# Redox1_1_Integration_Trial.net
KiCad netlist of a schematic drawn in EAGLE
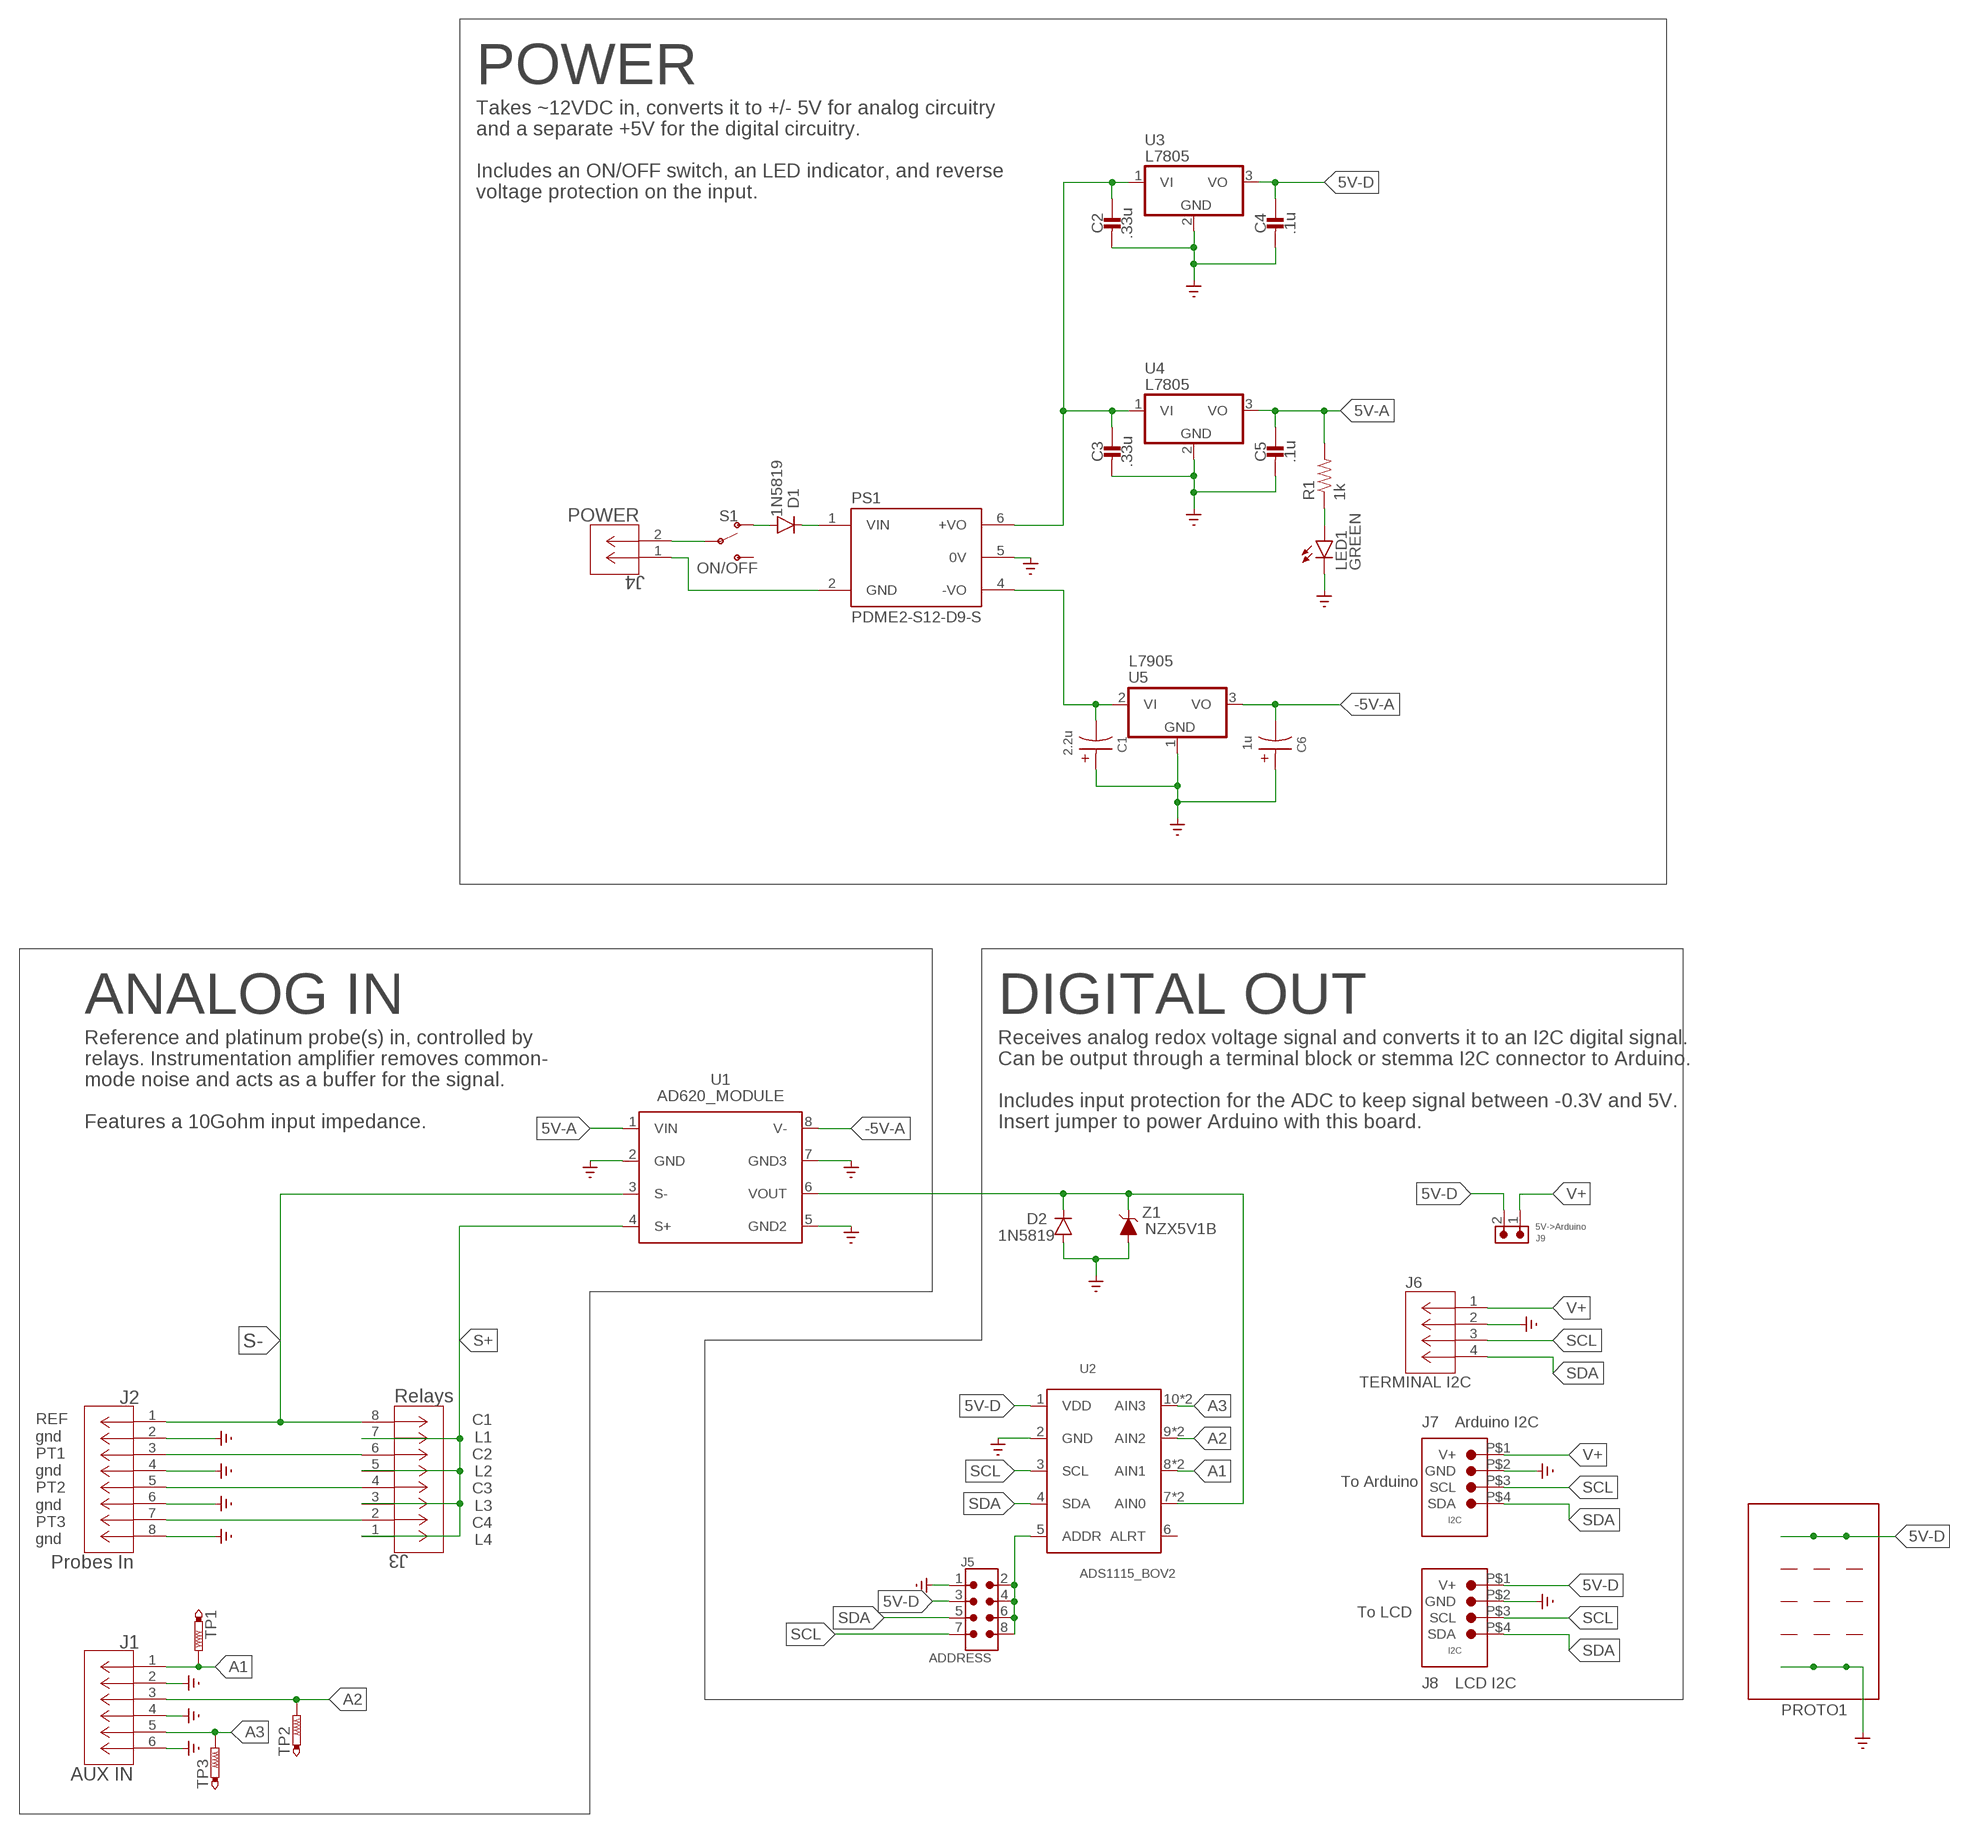
[diagram p0: schematic, sheet 1]

(export (version "E")
  (design (tool "Eeschema 10.0.6"))
  (components
    (comp (ref "C1")
      (value "2.2u")
      (footprint "eagle-import:E2,5-5")
      (libsource (lib "eagle-import") (part "CAP_POLAR_TH5MM"))
    )
    (comp (ref "C2")
      (value ".33u")
      (footprint "eagle-import:THCAPCERAMIC")
      (libsource (lib "eagle-import") (part "CAP-TH-CERAMIC"))
    )
    (comp (ref "C3")
      (value ".33u")
      (footprint "eagle-import:THCAPCERAMIC")
      (libsource (lib "eagle-import") (part "CAP-TH-CERAMIC"))
    )
    (comp (ref "C4")
      (value ".1u")
      (footprint "eagle-import:THCAPCERAMIC")
      (libsource (lib "eagle-import") (part "CAP-TH-CERAMIC"))
    )
    (comp (ref "C5")
      (value ".1u")
      (footprint "eagle-import:THCAPCERAMIC")
      (libsource (lib "eagle-import") (part "CAP-TH-CERAMIC"))
    )
    (comp (ref "C6")
      (value "1u")
      (footprint "eagle-import:E2,5-5")
      (libsource (lib "eagle-import") (part "CAP_POLAR_TH5MM"))
    )
    (comp (ref "D1")
      (value "1N5819")
      (footprint "eagle-import:DIODE-TH")
      (libsource (lib "eagle-import") (part "DIODE-TH"))
    )
    (comp (ref "D2")
      (value "1N5819")
      (footprint "eagle-import:DIODE-TH")
      (libsource (lib "eagle-import") (part "DIODE-TH"))
    )
    (comp (ref "J1")
      (value "AUX IN")
      (footprint "eagle-import:6PIN_TERMINAL_5MM")
      (libsource (lib "eagle-import") (part "6PIN_TERMINAL_5MM"))
    )
    (comp (ref "J2")
      (value "Probes In")
      (footprint "eagle-import:8PIN_TERMINAL_5MM")
      (libsource (lib "eagle-import") (part "8PIN_TERMINAL_5MM"))
    )
    (comp (ref "J3")
      (value "Relays")
      (footprint "eagle-import:8PIN_TERMINAL_5MM")
      (libsource (lib "eagle-import") (part "8PIN_TERMINAL_5MM"))
    )
    (comp (ref "J4")
      (value "POWER")
      (footprint "eagle-import:CONN2_710002_WRE")
      (fields
        (field (name "MANUFACTURER_PART_NUMBER") "691137710002")
        (field (name "COPYRIGHT") "Copyright (C) 2023 Ultra Librarian. All rights reserved.")
      )
      (libsource (lib "eagle-import") (part "2PIN_TERMINAL_5MM"))
    )
    (comp (ref "J5")
      (value "ADDRESS")
      (footprint "eagle-import:61300821121")
      (libsource (lib "eagle-import") (part "6130XX21121_61300821121"))
    )
    (comp (ref "J6")
      (value "TERMINAL I2C")
      (footprint "eagle-import:4PIN_TERMINAL_5MM")
      (libsource (lib "eagle-import") (part "4PIN_TERMINAL_5MM"))
    )
    (comp (ref "J7")
      (value "Arduino I2C")
      (footprint "eagle-import:JST_PH_4PIN")
      (libsource (lib "eagle-import") (part "JST_PH_4PIN_STEMMA"))
    )
    (comp (ref "J8")
      (value "LCD I2C")
      (footprint "eagle-import:JST_PH_4PIN")
      (libsource (lib "eagle-import") (part "JST_PH_4PIN_STEMMA"))
    )
    (comp (ref "J9")
      (value "5V->Arduino")
      (footprint "eagle-import:61300211121")
      (libsource (lib "eagle-import") (part "1X2MALEPIN"))
    )
    (comp (ref "LED1")
      (value "GREEN")
      (footprint "eagle-import:LED-5MM-TH")
      (libsource (lib "eagle-import") (part "LED-TH(5MM)"))
    )
    (comp (ref "PROTO1")
      (value "PROTO_AREA_5X3")
      (footprint "eagle-import:PROTO_AREA_5X3")
      (libsource (lib "eagle-import") (part "PROTO_AREA_5X3"))
    )
    (comp (ref "PS1")
      (value "PDME2-S12-D9-S")
      (footprint "eagle-import:CONV_PDME2-S12-D9-S")
      (fields (field (name "MANUFACTURER") "CUI Inc"))
      (libsource (lib "eagle-import") (part "PDME2-S12-D9-S"))
    )
    (comp (ref "R1")
      (value "1k")
      (footprint "eagle-import:THRESISTOR")
      (libsource (lib "eagle-import") (part "RESISTOR-TH"))
    )
    (comp (ref "S1")
      (value "ON/OFF")
      (footprint "eagle-import:TT11_SPDT")
      (libsource (lib "eagle-import") (part "SPDT_TT11_TH"))
    )
    (comp (ref "TP1")
      (value "PTR1PAD1-13")
      (footprint "eagle-import:P1-13")
      (libsource (lib "eagle-import") (part "PTR1PAD1-13"))
    )
    (comp (ref "TP2")
      (value "PTR1PAD1-13")
      (footprint "eagle-import:P1-13")
      (libsource (lib "eagle-import") (part "PTR1PAD1-13"))
    )
    (comp (ref "TP3")
      (value "PTR1PAD1-13")
      (footprint "eagle-import:P1-13")
      (libsource (lib "eagle-import") (part "PTR1PAD1-13"))
    )
    (comp (ref "U1")
      (value "AD620_MODULE")
      (footprint "eagle-import:AD620_MODULE")
      (libsource (lib "eagle-import") (part "AD620_MODULE"))
    )
    (comp (ref "U2")
      (value "ADS1115_BOV2")
      (footprint "eagle-import:ADS1115_V2")
      (libsource (lib "eagle-import") (part "ADS1115_BOV2"))
    )
    (comp (ref "U3")
      (value "L7805")
      (footprint "eagle-import:TO220V")
      (libsource (lib "eagle-import") (part "78TV05"))
    )
    (comp (ref "U4")
      (value "L7805")
      (footprint "eagle-import:TO220V")
      (libsource (lib "eagle-import") (part "78TV05"))
    )
    (comp (ref "U5")
      (value "L7905")
      (footprint "eagle-import:TO220V")
      (libsource (lib "eagle-import") (part "L79REGULATORTO220V"))
    )
    (comp (ref "Z1")
      (value "NZX5V1B")
      (footprint "eagle-import:DIODE-TH")
      (libsource (lib "eagle-import") (part "ZENER"))
    )
  )
  (nets
    (net (code "1") (name "-5V-A") (class "Default")
      (node (ref "C6") (pin "-") (pinfunction "-_-") (pintype "passive"))
      (node (ref "U1") (pin "8") (pinfunction "V-_8") (pintype "bidirectional"))
      (node (ref "U5") (pin "3") (pinfunction "VO_3") (pintype "passive"))
    )
    (net (code "2") (name "5V-A") (class "Default")
      (node (ref "C5") (pin "C1") (pinfunction "1_C1") (pintype "passive"))
      (node (ref "R1") (pin "R2") (pinfunction "2_R2") (pintype "passive"))
      (node (ref "U1") (pin "1") (pinfunction "VIN_1") (pintype "bidirectional"))
      (node (ref "U4") (pin "3") (pinfunction "VO_3") (pintype "passive"))
    )
    (net (code "3") (name "5V-D") (class "Default")
      (node (ref "C4") (pin "C1") (pinfunction "1_C1") (pintype "passive"))
      (node (ref "J5") (pin "3") (pinfunction "3_3") (pintype "passive"))
      (node (ref "J8") (pin "P$1") (pinfunction "V+_P$1") (pintype "bidirectional"))
      (node (ref "J9") (pin "2") (pinfunction "2_2") (pintype "passive"))
      (node (ref "PROTO1") (pin "1") (pinfunction "1_1") (pintype "bidirectional"))
      (node (ref "PROTO1") (pin "2") (pinfunction "2_2") (pintype "bidirectional"))
      (node (ref "PROTO1") (pin "3") (pinfunction "3_3") (pintype "bidirectional"))
      (node (ref "U2") (pin "1") (pinfunction "VDD_1") (pintype "bidirectional"))
      (node (ref "U3") (pin "3") (pinfunction "VO_3") (pintype "passive"))
    )
    (net (code "4") (name "A1") (class "Default")
      (node (ref "J1") (pin "1") (pinfunction "1_1") (pintype "passive"))
      (node (ref "TP1") (pin "TP") (pinfunction "TP_TP") (pintype "input"))
      (node (ref "U2") (pin "8") (pinfunction "AIN1_8") (pintype "bidirectional"))
      (node (ref "U2") (pin "A1") (pinfunction "AIN1_A1") (pintype "bidirectional"))
    )
    (net (code "5") (name "A2") (class "Default")
      (node (ref "J1") (pin "3") (pinfunction "3_3") (pintype "passive"))
      (node (ref "TP2") (pin "TP") (pinfunction "TP_TP") (pintype "input"))
      (node (ref "U2") (pin "9") (pinfunction "AIN2_9") (pintype "bidirectional"))
      (node (ref "U2") (pin "A2") (pinfunction "AIN2_A2") (pintype "bidirectional"))
    )
    (net (code "6") (name "A3") (class "Default")
      (node (ref "J1") (pin "5") (pinfunction "5_5") (pintype "passive"))
      (node (ref "TP3") (pin "TP") (pinfunction "TP_TP") (pintype "input"))
      (node (ref "U2") (pin "10") (pinfunction "AIN3_10") (pintype "bidirectional"))
      (node (ref "U2") (pin "A3") (pinfunction "AIN3_A3") (pintype "bidirectional"))
    )
    (net (code "7") (name "Net-(C2-1)") (class "Default")
      (node (ref "C2") (pin "C1") (pinfunction "1_C1") (pintype "passive"))
      (node (ref "C3") (pin "C1") (pinfunction "1_C1") (pintype "passive"))
      (node (ref "PS1") (pin "6") (pinfunction "+VO_6") (pintype "output"))
      (node (ref "U3") (pin "1") (pinfunction "VI_1") (pintype "input"))
      (node (ref "U4") (pin "1") (pinfunction "VI_1") (pintype "input"))
    )
    (net (code "8") (name "Net-(D1-A)") (class "Default")
      (node (ref "D1") (pin "P$1") (pinfunction "A_P$1") (pintype "passive"))
      (node (ref "S1") (pin "P$1") (pinfunction "1_P$1") (pintype "passive"))
    )
    (net (code "9") (name "Net-(D1-C)") (class "Default")
      (node (ref "D1") (pin "P$2") (pinfunction "C_P$2") (pintype "passive"))
      (node (ref "PS1") (pin "1") (pinfunction "VIN_1") (pintype "input"))
    )
    (net (code "10") (name "Net-(D2-C)") (class "Default")
      (node (ref "D2") (pin "P$2") (pinfunction "C_P$2") (pintype "passive"))
      (node (ref "U1") (pin "6") (pinfunction "VOUT_6") (pintype "bidirectional"))
      (node (ref "U2") (pin "7") (pinfunction "AIN0_7") (pintype "bidirectional"))
      (node (ref "U2") (pin "A0") (pinfunction "AIN0_A0") (pintype "bidirectional"))
      (node (ref "Z1") (pin "P$2") (pinfunction "C_P$2") (pintype "passive"))
    )
    (net (code "11") (name "Net-(J2-Pad3)") (class "Default")
      (node (ref "J2") (pin "3") (pinfunction "3_3") (pintype "passive"))
      (node (ref "J3") (pin "6") (pinfunction "6_6") (pintype "passive"))
    )
    (net (code "12") (name "Net-(J2-Pad5)") (class "Default")
      (node (ref "J2") (pin "5") (pinfunction "5_5") (pintype "passive"))
      (node (ref "J3") (pin "4") (pinfunction "4_4") (pintype "passive"))
    )
    (net (code "13") (name "Net-(J2-Pad7)") (class "Default")
      (node (ref "J2") (pin "7") (pinfunction "7_7") (pintype "passive"))
      (node (ref "J3") (pin "2") (pinfunction "2_2") (pintype "passive"))
    )
    (net (code "14") (name "Net-(PS1--VO)") (class "Default")
      (node (ref "C1") (pin "-") (pinfunction "-_-") (pintype "passive"))
      (node (ref "PS1") (pin "4") (pinfunction "-VO_4") (pintype "output"))
      (node (ref "U5") (pin "2") (pinfunction "VI_2") (pintype "input"))
    )
    (net (code "15") (name "Net-(PS1-GND)") (class "Default")
      (node (ref "J4") (pin "1") (pinfunction "1_1") (pintype "passive"))
      (node (ref "PS1") (pin "2") (pinfunction "GND_2") (pintype "power_in"))
    )
    (net (code "16") (name "Net-(R1-1)") (class "Default")
      (node (ref "LED1") (pin "A") (pinfunction "A_A") (pintype "passive"))
      (node (ref "R1") (pin "R1") (pinfunction "1_R1") (pintype "passive"))
    )
    (net (code "17") (name "Net-(S1-C)") (class "Default")
      (node (ref "J4") (pin "2") (pinfunction "2_2") (pintype "passive"))
      (node (ref "S1") (pin "P$2") (pinfunction "C_P$2") (pintype "passive"))
    )
    (net (code "18") (name "Net-(U2-ADDR)") (class "Default")
      (node (ref "J5") (pin "2") (pinfunction "2_2") (pintype "passive"))
      (node (ref "J5") (pin "4") (pinfunction "4_4") (pintype "passive"))
      (node (ref "J5") (pin "6") (pinfunction "6_6") (pintype "passive"))
      (node (ref "J5") (pin "8") (pinfunction "8_8") (pintype "passive"))
      (node (ref "U2") (pin "5") (pinfunction "ADDR_5") (pintype "bidirectional"))
    )
    (net (code "19") (name "S+") (class "Default")
      (node (ref "J3") (pin "1") (pinfunction "1_1") (pintype "passive"))
      (node (ref "J3") (pin "3") (pinfunction "3_3") (pintype "passive"))
      (node (ref "J3") (pin "5") (pinfunction "5_5") (pintype "passive"))
      (node (ref "J3") (pin "7") (pinfunction "7_7") (pintype "passive"))
      (node (ref "U1") (pin "4") (pinfunction "S+_4") (pintype "bidirectional"))
    )
    (net (code "20") (name "S-") (class "Default")
      (node (ref "J2") (pin "1") (pinfunction "1_1") (pintype "passive"))
      (node (ref "J3") (pin "8") (pinfunction "8_8") (pintype "passive"))
      (node (ref "U1") (pin "3") (pinfunction "S-_3") (pintype "bidirectional"))
    )
    (net (code "21") (name "SCL") (class "Default")
      (node (ref "J5") (pin "7") (pinfunction "7_7") (pintype "passive"))
      (node (ref "J6") (pin "3") (pinfunction "3_3") (pintype "passive"))
      (node (ref "J7") (pin "P$3") (pinfunction "SCL_P$3") (pintype "bidirectional"))
      (node (ref "J8") (pin "P$3") (pinfunction "SCL_P$3") (pintype "bidirectional"))
      (node (ref "U2") (pin "3") (pinfunction "SCL_3") (pintype "bidirectional"))
    )
    (net (code "22") (name "SDA") (class "Default")
      (node (ref "J5") (pin "5") (pinfunction "5_5") (pintype "passive"))
      (node (ref "J6") (pin "4") (pinfunction "4_4") (pintype "passive"))
      (node (ref "J7") (pin "P$4") (pinfunction "SDA_P$4") (pintype "bidirectional"))
      (node (ref "J8") (pin "P$4") (pinfunction "SDA_P$4") (pintype "bidirectional"))
      (node (ref "U2") (pin "4") (pinfunction "SDA_4") (pintype "bidirectional"))
    )
    (net (code "23") (name "SUPPLY0_GND_") (class "Default")
      (node (ref "C1") (pin "+") (pinfunction "+_+") (pintype "passive"))
      (node (ref "C2") (pin "C2") (pinfunction "2_C2") (pintype "passive"))
      (node (ref "C3") (pin "C2") (pinfunction "2_C2") (pintype "passive"))
      (node (ref "C4") (pin "C2") (pinfunction "2_C2") (pintype "passive"))
      (node (ref "C5") (pin "C2") (pinfunction "2_C2") (pintype "passive"))
      (node (ref "C6") (pin "+") (pinfunction "+_+") (pintype "passive"))
      (node (ref "D2") (pin "P$1") (pinfunction "A_P$1") (pintype "passive"))
      (node (ref "J1") (pin "2") (pinfunction "2_2") (pintype "passive"))
      (node (ref "J1") (pin "4") (pinfunction "4_4") (pintype "passive"))
      (node (ref "J1") (pin "6") (pinfunction "6_6") (pintype "passive"))
      (node (ref "J2") (pin "2") (pinfunction "2_2") (pintype "passive"))
      (node (ref "J2") (pin "4") (pinfunction "4_4") (pintype "passive"))
      (node (ref "J2") (pin "6") (pinfunction "6_6") (pintype "passive"))
      (node (ref "J2") (pin "8") (pinfunction "8_8") (pintype "passive"))
      (node (ref "J5") (pin "1") (pinfunction "1_1") (pintype "passive"))
      (node (ref "J6") (pin "2") (pinfunction "2_2") (pintype "passive"))
      (node (ref "J7") (pin "P$2") (pinfunction "GND_P$2") (pintype "bidirectional"))
      (node (ref "J8") (pin "P$2") (pinfunction "GND_P$2") (pintype "bidirectional"))
      (node (ref "LED1") (pin "K") (pinfunction "C_K") (pintype "passive"))
      (node (ref "PROTO1") (pin "13") (pinfunction "13_13") (pintype "bidirectional"))
      (node (ref "PROTO1") (pin "14") (pinfunction "14_14") (pintype "bidirectional"))
      (node (ref "PROTO1") (pin "15") (pinfunction "15_15") (pintype "bidirectional"))
      (node (ref "PS1") (pin "5") (pinfunction "0V_5") (pintype "output"))
      (node (ref "U1") (pin "2") (pinfunction "GND_2") (pintype "bidirectional"))
      (node (ref "U1") (pin "5") (pinfunction "GND2_5") (pintype "bidirectional"))
      (node (ref "U1") (pin "7") (pinfunction "GND3_7") (pintype "bidirectional"))
      (node (ref "U2") (pin "2") (pinfunction "GND_2") (pintype "bidirectional"))
      (node (ref "U3") (pin "2") (pinfunction "GND_2") (pintype "passive"))
      (node (ref "U4") (pin "2") (pinfunction "GND_2") (pintype "passive"))
      (node (ref "U5") (pin "1") (pinfunction "GND_1") (pintype "passive"))
      (node (ref "Z1") (pin "P$1") (pinfunction "A_P$1") (pintype "passive"))
    )
    (net (code "24") (name "V+") (class "Default")
      (node (ref "J6") (pin "1") (pinfunction "1_1") (pintype "passive"))
      (node (ref "J7") (pin "P$1") (pinfunction "V+_P$1") (pintype "bidirectional"))
      (node (ref "J9") (pin "1") (pinfunction "1_1") (pintype "passive"))
    )
    (net (code "25") (name "unconnected-(PROTO1-Pad4)") (class "Default")
      (node (ref "PROTO1") (pin "4") (pinfunction "4_4") (pintype "bidirectional"))
    )
    (net (code "26") (name "unconnected-(PROTO1-Pad5)") (class "Default")
      (node (ref "PROTO1") (pin "5") (pinfunction "5_5") (pintype "bidirectional"))
    )
    (net (code "27") (name "unconnected-(PROTO1-Pad6)") (class "Default")
      (node (ref "PROTO1") (pin "6") (pinfunction "6_6") (pintype "bidirectional"))
    )
    (net (code "28") (name "unconnected-(PROTO1-Pad7)") (class "Default")
      (node (ref "PROTO1") (pin "7") (pinfunction "7_7") (pintype "bidirectional"))
    )
    (net (code "29") (name "unconnected-(PROTO1-Pad8)") (class "Default")
      (node (ref "PROTO1") (pin "8") (pinfunction "8_8") (pintype "bidirectional"))
    )
    (net (code "30") (name "unconnected-(PROTO1-Pad9)") (class "Default")
      (node (ref "PROTO1") (pin "9") (pinfunction "9_9") (pintype "bidirectional"))
    )
    (net (code "31") (name "unconnected-(PROTO1-Pad10)") (class "Default")
      (node (ref "PROTO1") (pin "10") (pinfunction "10_10") (pintype "bidirectional"))
    )
    (net (code "32") (name "unconnected-(PROTO1-Pad11)") (class "Default")
      (node (ref "PROTO1") (pin "11") (pinfunction "11_11") (pintype "bidirectional"))
    )
    (net (code "33") (name "unconnected-(PROTO1-Pad12)") (class "Default")
      (node (ref "PROTO1") (pin "12") (pinfunction "12_12") (pintype "bidirectional"))
    )
    (net (code "34") (name "unconnected-(S1-3-PadP$3)") (class "Default")
      (node (ref "S1") (pin "P$3") (pinfunction "3_P$3") (pintype "passive"))
    )
    (net (code "35") (name "unconnected-(U2-ALRT-Pad6)") (class "Default")
      (node (ref "U2") (pin "6") (pinfunction "ALRT_6") (pintype "bidirectional"))
    )
  )
)
